# humidity_brick.net
KiCad netlist of a schematic drawn in EAGLE
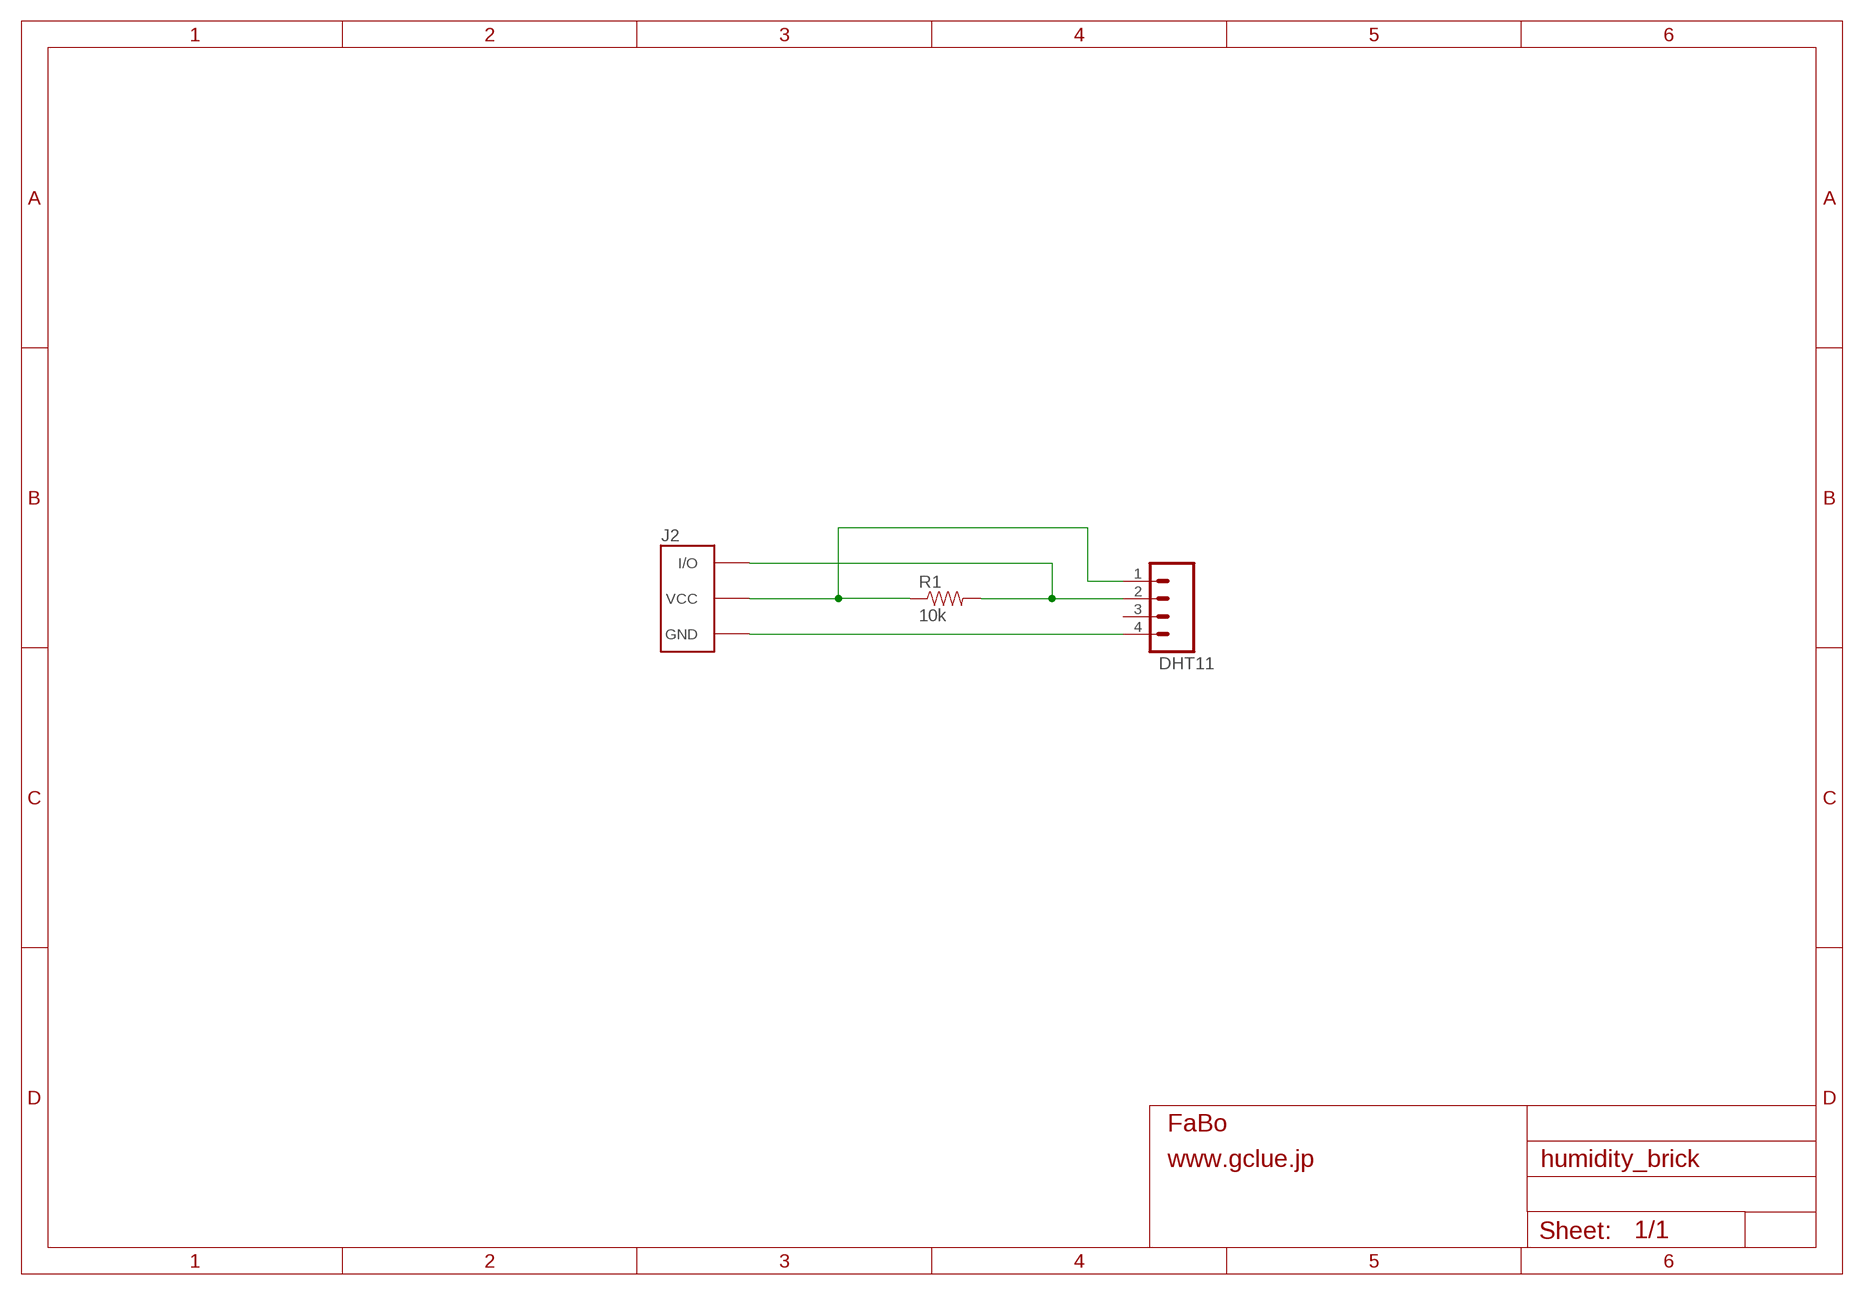
[diagram p0: schematic, sheet 1]

(export (version "E")
  (design (tool "Eeschema 10.0.6"))
  (components
    (comp (ref "J2")
      (value "BRICK_3PIN")
      (footprint "eagle-import:BRICK_3PIN")
      (libsource (lib "eagle-import") (part "BRICK_3PIN"))
    )
    (comp (ref "JP1")
      (value "DHT11")
      (footprint "eagle-import:1X04_LONGPADS")
      (libsource (lib "eagle-import") (part "M04LONGPADS"))
    )
    (comp (ref "R1")
      (value "10k")
      (footprint "eagle-import:AXIAL-0.4")
      (libsource (lib "eagle-import") (part "RESISTORPTH-1/4W"))
    )
  )
  (nets
    (net (code "1") (name "Net-(J2-I{slash}O)") (class "Default")
      (node (ref "J2") (pin "IN/OUT") (pinfunction "I/O_IN/OUT") (pintype "bidirectional"))
      (node (ref "JP1") (pin "2") (pinfunction "2_2") (pintype "passive"))
      (node (ref "R1") (pin "P$2") (pinfunction "2_P$2") (pintype "passive"))
    )
    (net (code "2") (name "Net-(J2-PadGND)") (class "Default")
      (node (ref "J2") (pin "GND") (pinfunction "GND_GND") (pintype "bidirectional"))
      (node (ref "JP1") (pin "4") (pinfunction "4_4") (pintype "passive"))
    )
    (net (code "3") (name "Net-(R1-1)") (class "Default")
      (node (ref "J2") (pin "VCC") (pinfunction "VCC_VCC") (pintype "bidirectional"))
      (node (ref "JP1") (pin "1") (pinfunction "1_1") (pintype "passive"))
      (node (ref "R1") (pin "P$1") (pinfunction "1_P$1") (pintype "passive"))
    )
    (net (code "4") (name "unconnected-(JP1-Pad3)") (class "Default")
      (node (ref "JP1") (pin "3") (pinfunction "3_3") (pintype "passive"))
    )
  )
)
